# main.net
KiCad netlist of a schematic drawn in EAGLE
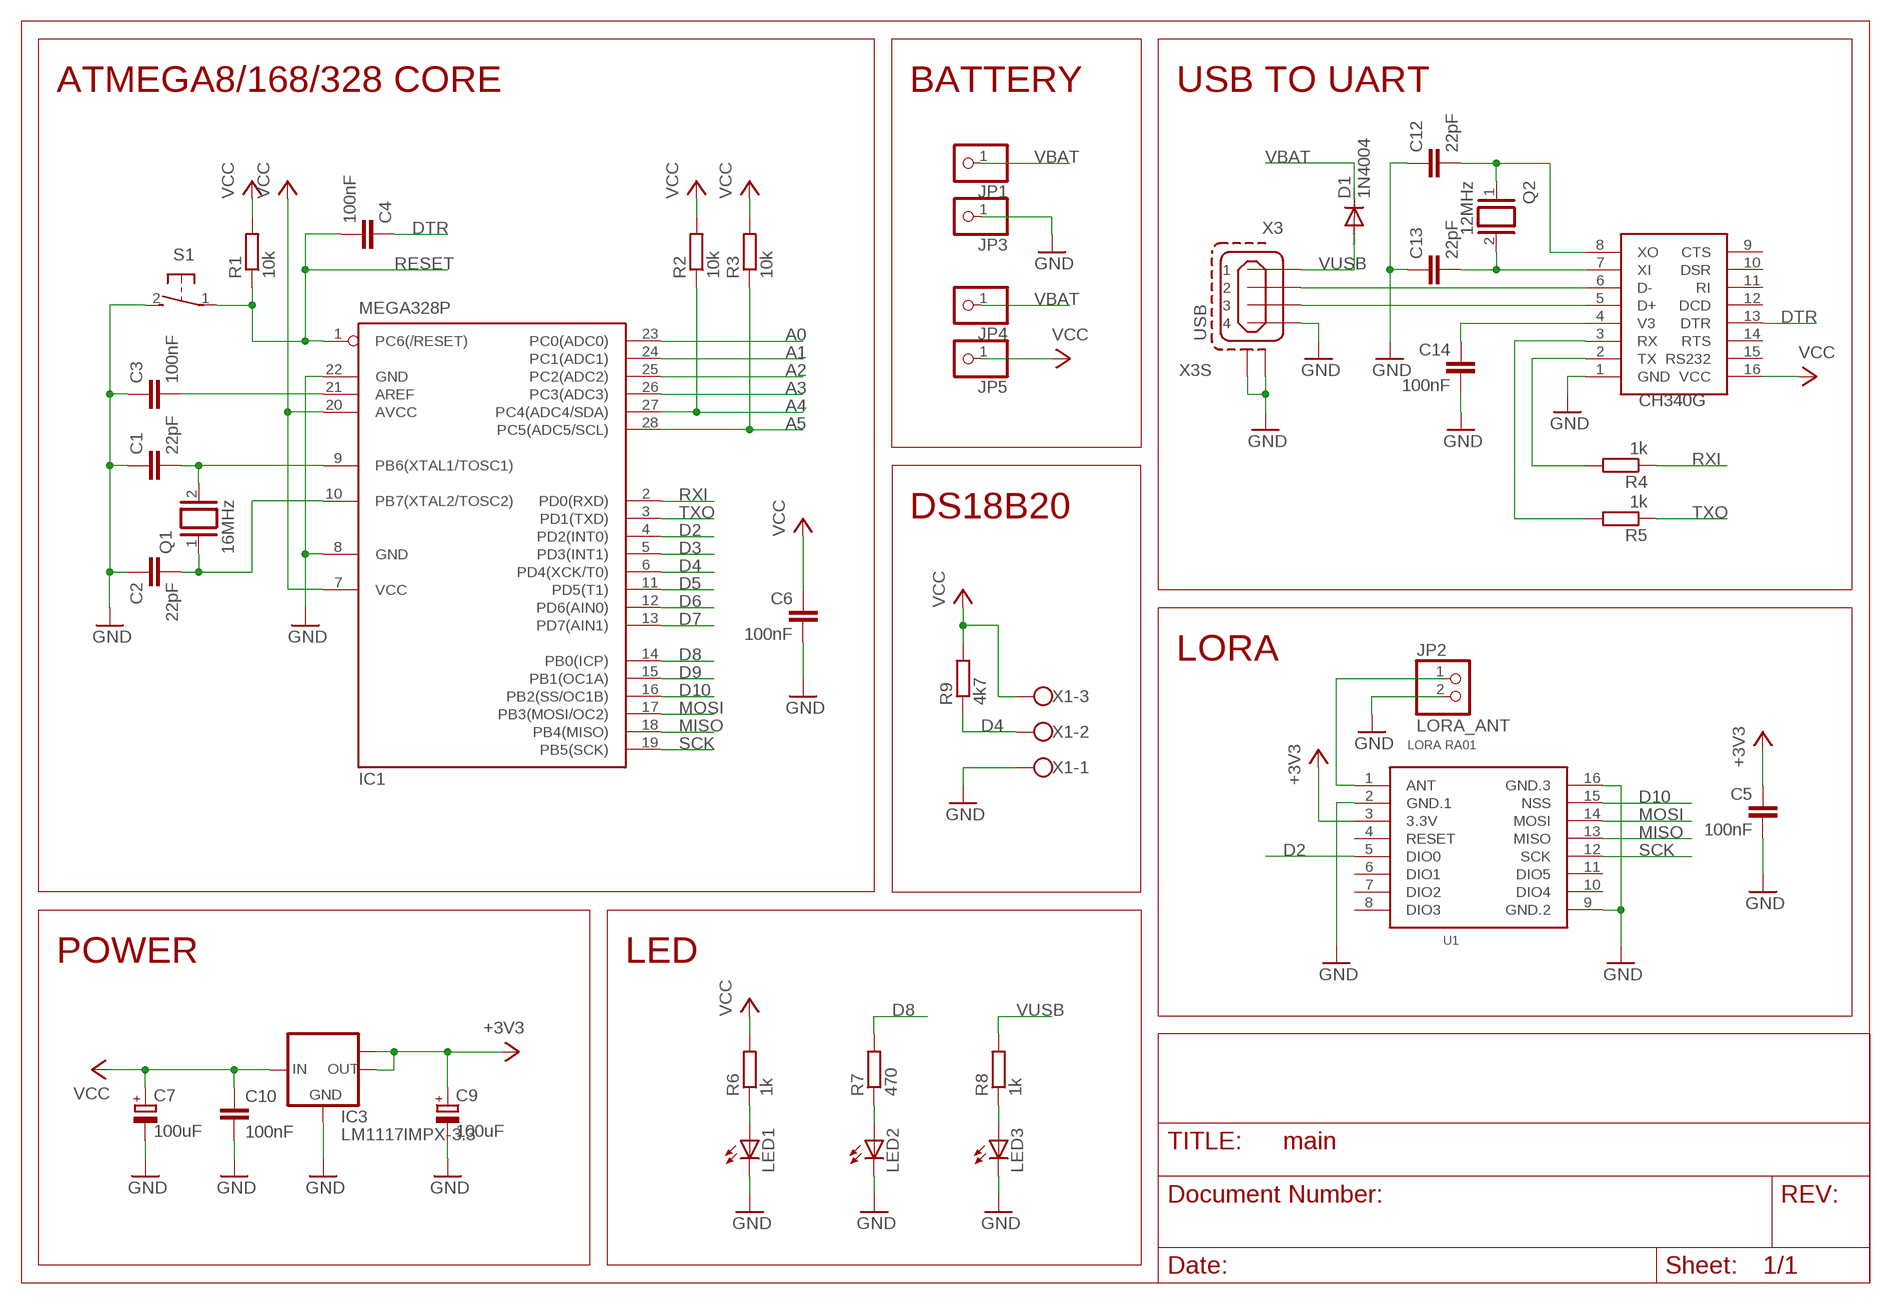
[diagram p0: schematic, sheet 1]

(export (version "E")
  (design (tool "Eeschema 10.0.6"))
  (components
    (comp (ref "C1")
      (value "22pF")
      (footprint "eagle-import:C050-024X044")
      (libsource (lib "eagle-import") (part "C-EU050-024X044"))
    )
    (comp (ref "C2")
      (value "22pF")
      (footprint "eagle-import:C050-024X044")
      (libsource (lib "eagle-import") (part "C-EU050-024X044"))
    )
    (comp (ref "C3")
      (value "100nF")
      (footprint "eagle-import:C050-024X044")
      (libsource (lib "eagle-import") (part "C-EU050-024X044"))
    )
    (comp (ref "C4")
      (value "100nF")
      (footprint "eagle-import:C050-024X044")
      (libsource (lib "eagle-import") (part "C-EU050-024X044"))
    )
    (comp (ref "C5")
      (value "100nF")
      (footprint "eagle-import:C050-024X044")
      (libsource (lib "eagle-import") (part "C-EU050-024X044"))
    )
    (comp (ref "C6")
      (value "100nF")
      (footprint "eagle-import:C050-024X044")
      (libsource (lib "eagle-import") (part "C-EU050-024X044"))
    )
    (comp (ref "C7")
      (value "100uF")
      (footprint "eagle-import:E3,5-10")
      (libsource (lib "eagle-import") (part "CPOL-EUE3.5-10"))
    )
    (comp (ref "C9")
      (value "100uF")
      (footprint "eagle-import:E3,5-8")
      (libsource (lib "eagle-import") (part "CPOL-EUE3.5-8"))
    )
    (comp (ref "C10")
      (value "100nF")
      (footprint "eagle-import:C050-024X044")
      (libsource (lib "eagle-import") (part "C-EU050-024X044"))
    )
    (comp (ref "C12")
      (value "22pF")
      (footprint "eagle-import:C050-024X044")
      (libsource (lib "eagle-import") (part "C-EU050-024X044"))
    )
    (comp (ref "C13")
      (value "22pF")
      (footprint "eagle-import:C050-024X044")
      (libsource (lib "eagle-import") (part "C-EU050-024X044"))
    )
    (comp (ref "C14")
      (value "100nF")
      (footprint "eagle-import:C050-024X044")
      (libsource (lib "eagle-import") (part "C-EU050-024X044"))
    )
    (comp (ref "D1")
      (value "1N4004")
      (footprint "eagle-import:DO41-10")
      (libsource (lib "eagle-import") (part "1N4004"))
    )
    (comp (ref "IC1")
      (value "MEGA328P")
      (footprint "eagle-import:DIL28-3")
      (libsource (lib "eagle-import") (part "MEGA8-P"))
    )
    (comp (ref "IC3")
      (value "LM1117IMPX-3.3")
      (footprint "eagle-import:SOT223")
      (libsource (lib "eagle-import") (part "LM1117IMPX-3.3"))
    )
    (comp (ref "JP1")
      (value "PINHD-1X1")
      (footprint "eagle-import:1X01")
      (libsource (lib "eagle-import") (part "PINHD-1X1"))
    )
    (comp (ref "JP2")
      (value "LORA_ANT")
      (footprint "eagle-import:1X02")
      (libsource (lib "eagle-import") (part "PINHD-1X2"))
    )
    (comp (ref "JP3")
      (value "PINHD-1X1")
      (footprint "eagle-import:1X01")
      (libsource (lib "eagle-import") (part "PINHD-1X1"))
    )
    (comp (ref "JP4")
      (value "PINHD-1X1")
      (footprint "eagle-import:1X01")
      (libsource (lib "eagle-import") (part "PINHD-1X1"))
    )
    (comp (ref "JP5")
      (value "PINHD-1X1")
      (footprint "eagle-import:1X01")
      (libsource (lib "eagle-import") (part "PINHD-1X1"))
    )
    (comp (ref "LED1")
      (value "LED3MM")
      (footprint "eagle-import:LED3MM")
      (libsource (lib "eagle-import") (part "LED3MM"))
    )
    (comp (ref "LED2")
      (value "LED3MM")
      (footprint "eagle-import:LED3MM")
      (libsource (lib "eagle-import") (part "LED3MM"))
    )
    (comp (ref "LED3")
      (value "LED3MM")
      (footprint "eagle-import:LED3MM")
      (libsource (lib "eagle-import") (part "LED3MM"))
    )
    (comp (ref "Q1")
      (value "16MHz")
      (footprint "eagle-import:QS")
      (libsource (lib "eagle-import") (part "XTAL/S"))
    )
    (comp (ref "Q2")
      (value "12MHz")
      (footprint "eagle-import:QS")
      (libsource (lib "eagle-import") (part "XTAL/S"))
    )
    (comp (ref "R1")
      (value "10k")
      (footprint "eagle-import:0207_10")
      (libsource (lib "eagle-import") (part "R-EU_0207/10"))
    )
    (comp (ref "R2")
      (value "10k")
      (footprint "eagle-import:0207_10")
      (libsource (lib "eagle-import") (part "R-EU_0207/10"))
    )
    (comp (ref "R3")
      (value "10k")
      (footprint "eagle-import:0207_10")
      (libsource (lib "eagle-import") (part "R-EU_0207/10"))
    )
    (comp (ref "R4")
      (value "1k")
      (footprint "eagle-import:0207_10")
      (libsource (lib "eagle-import") (part "R-EU_0207/10"))
    )
    (comp (ref "R5")
      (value "1k")
      (footprint "eagle-import:0207_10")
      (libsource (lib "eagle-import") (part "R-EU_0207/10"))
    )
    (comp (ref "R6")
      (value "1k")
      (footprint "eagle-import:0207_10")
      (libsource (lib "eagle-import") (part "R-EU_0207/10"))
    )
    (comp (ref "R7")
      (value "470")
      (footprint "eagle-import:0207_10")
      (libsource (lib "eagle-import") (part "R-EU_0207/10"))
    )
    (comp (ref "R8")
      (value "1k")
      (footprint "eagle-import:0207_10")
      (libsource (lib "eagle-import") (part "R-EU_0207/10"))
    )
    (comp (ref "R9")
      (value "4k7")
      (footprint "eagle-import:0207_10")
      (libsource (lib "eagle-import") (part "R-EU_0207/10"))
    )
    (comp (ref "S1")
      (value "31-XX")
      (footprint "eagle-import:B3F-31XX")
      (fields (field (name "MPN") "B3F-3100"))
      (libsource (lib "eagle-import") (part "31-XX"))
    )
    (comp (ref "U$1")
      (value "CH340G")
      (footprint "eagle-import:SOIC16")
      (libsource (lib "eagle-import") (part "CH340G"))
    )
    (comp (ref "U1")
      (value "LORA RA01")
      (footprint "eagle-import:LORA-RA1-SMD")
      (libsource (lib "eagle-import") (part "LORA-RA-01-433MHZ"))
    )
    (comp (ref "X1")
      (value "W237-103")
      (footprint "eagle-import:W237-103")
      (fields (field (name "MPN") "237-103"))
      (libsource (lib "eagle-import") (part "W237-103"))
    )
    (comp (ref "X3")
      (value "USB")
      (footprint "eagle-import:85-32004-00X")
      (libsource (lib "eagle-import") (part "MINI-USB_SHIELD4P-85-32004-00X"))
    )
  )
  (nets
    (net (code "1") (name "+3V3") (class "Default")
      (node (ref "C5") (pin "1") (pinfunction "1_1") (pintype "passive"))
      (node (ref "C9") (pin "+") (pinfunction "+_+") (pintype "passive"))
      (node (ref "IC3") (pin "2") (pinfunction "OUT_2") (pintype "passive"))
      (node (ref "IC3") (pin "TAB") (pinfunction "OUT1_TAB") (pintype "passive"))
      (node (ref "U1") (pin "3") (pinfunction "3.3V_3") (pintype "power_in"))
    )
    (net (code "2") (name "/A0") (class "Default")
      (node (ref "IC1") (pin "23") (pinfunction "PC0(ADC0)_23") (pintype "bidirectional"))
    )
    (net (code "3") (name "/A1") (class "Default")
      (node (ref "IC1") (pin "24") (pinfunction "PC1(ADC1)_24") (pintype "bidirectional"))
    )
    (net (code "4") (name "/A2") (class "Default")
      (node (ref "IC1") (pin "25") (pinfunction "PC2(ADC2)_25") (pintype "bidirectional"))
    )
    (net (code "5") (name "/A3") (class "Default")
      (node (ref "IC1") (pin "26") (pinfunction "PC3(ADC3)_26") (pintype "bidirectional"))
    )
    (net (code "6") (name "/A4") (class "Default")
      (node (ref "IC1") (pin "27") (pinfunction "PC4(ADC4/SDA)_27") (pintype "bidirectional"))
      (node (ref "R2") (pin "1") (pinfunction "1_1") (pintype "passive"))
    )
    (net (code "7") (name "/A5") (class "Default")
      (node (ref "IC1") (pin "28") (pinfunction "PC5(ADC5/SCL)_28") (pintype "bidirectional"))
      (node (ref "R3") (pin "1") (pinfunction "1_1") (pintype "passive"))
    )
    (net (code "8") (name "/D2") (class "Default")
      (node (ref "IC1") (pin "4") (pinfunction "PD2(INT0)_4") (pintype "bidirectional"))
      (node (ref "U1") (pin "5") (pinfunction "DIO0_5") (pintype "bidirectional"))
    )
    (net (code "9") (name "/D3") (class "Default")
      (node (ref "IC1") (pin "5") (pinfunction "PD3(INT1)_5") (pintype "bidirectional"))
    )
    (net (code "10") (name "/D4") (class "Default")
      (node (ref "IC1") (pin "6") (pinfunction "PD4(XCK/T0)_6") (pintype "bidirectional"))
      (node (ref "R9") (pin "1") (pinfunction "1_1") (pintype "passive"))
      (node (ref "X1") (pin "2") (pinfunction "KL_2") (pintype "passive"))
    )
    (net (code "11") (name "/D5") (class "Default")
      (node (ref "IC1") (pin "11") (pinfunction "PD5(T1)_11") (pintype "bidirectional"))
    )
    (net (code "12") (name "/D6") (class "Default")
      (node (ref "IC1") (pin "12") (pinfunction "PD6(AIN0)_12") (pintype "bidirectional"))
    )
    (net (code "13") (name "/D7") (class "Default")
      (node (ref "IC1") (pin "13") (pinfunction "PD7(AIN1)_13") (pintype "bidirectional"))
    )
    (net (code "14") (name "/D8") (class "Default")
      (node (ref "IC1") (pin "14") (pinfunction "PB0(ICP)_14") (pintype "bidirectional"))
      (node (ref "R7") (pin "2") (pinfunction "2_2") (pintype "passive"))
    )
    (net (code "15") (name "/D9") (class "Default")
      (node (ref "IC1") (pin "15") (pinfunction "PB1(OC1A)_15") (pintype "bidirectional"))
    )
    (net (code "16") (name "/D10") (class "Default")
      (node (ref "IC1") (pin "16") (pinfunction "PB2(SS/OC1B)_16") (pintype "bidirectional"))
      (node (ref "U1") (pin "15") (pinfunction "NSS_15") (pintype "bidirectional"))
    )
    (net (code "17") (name "/DTR") (class "Default")
      (node (ref "C4") (pin "1") (pinfunction "1_1") (pintype "passive"))
      (node (ref "U$1") (pin "13") (pinfunction "DTR_13") (pintype "bidirectional"))
    )
    (net (code "18") (name "/MISO") (class "Default")
      (node (ref "IC1") (pin "18") (pinfunction "PB4(MISO)_18") (pintype "bidirectional"))
      (node (ref "U1") (pin "13") (pinfunction "MISO_13") (pintype "bidirectional"))
    )
    (net (code "19") (name "/MOSI") (class "Default")
      (node (ref "IC1") (pin "17") (pinfunction "PB3(MOSI/OC2)_17") (pintype "bidirectional"))
      (node (ref "U1") (pin "14") (pinfunction "MOSI_14") (pintype "bidirectional"))
    )
    (net (code "20") (name "/RESET") (class "Default")
      (node (ref "C4") (pin "2") (pinfunction "2_2") (pintype "passive"))
      (node (ref "IC1") (pin "1") (pinfunction "PC6(/RESET)_1") (pintype "bidirectional"))
      (node (ref "R1") (pin "1") (pinfunction "1_1") (pintype "passive"))
      (node (ref "S1") (pin "1") (pinfunction "P_1") (pintype "passive"))
    )
    (net (code "21") (name "/RXI") (class "Default")
      (node (ref "IC1") (pin "2") (pinfunction "PD0(RXD)_2") (pintype "bidirectional"))
      (node (ref "R4") (pin "1") (pinfunction "1_1") (pintype "passive"))
    )
    (net (code "22") (name "/SCK") (class "Default")
      (node (ref "IC1") (pin "19") (pinfunction "PB5(SCK)_19") (pintype "bidirectional"))
      (node (ref "U1") (pin "12") (pinfunction "SCK_12") (pintype "bidirectional"))
    )
    (net (code "23") (name "/TXO") (class "Default")
      (node (ref "IC1") (pin "3") (pinfunction "PD1(TXD)_3") (pintype "bidirectional"))
      (node (ref "R5") (pin "1") (pinfunction "1_1") (pintype "passive"))
    )
    (net (code "24") (name "/VBAT") (class "Default")
      (node (ref "D1") (pin "C") (pinfunction "C_C") (pintype "passive"))
      (node (ref "JP1") (pin "1") (pinfunction "1_1") (pintype "passive"))
      (node (ref "JP4") (pin "1") (pinfunction "1_1") (pintype "passive"))
    )
    (net (code "25") (name "/VUSB") (class "Default")
      (node (ref "D1") (pin "A") (pinfunction "A_A") (pintype "passive"))
      (node (ref "R8") (pin "2") (pinfunction "2_2") (pintype "passive"))
      (node (ref "X3") (pin "1") (pinfunction "1_1") (pintype "passive"))
    )
    (net (code "26") (name "GND") (class "Default")
      (node (ref "C1") (pin "1") (pinfunction "1_1") (pintype "passive"))
      (node (ref "C10") (pin "2") (pinfunction "2_2") (pintype "passive"))
      (node (ref "C12") (pin "1") (pinfunction "1_1") (pintype "passive"))
      (node (ref "C13") (pin "1") (pinfunction "1_1") (pintype "passive"))
      (node (ref "C14") (pin "2") (pinfunction "2_2") (pintype "passive"))
      (node (ref "C2") (pin "1") (pinfunction "1_1") (pintype "passive"))
      (node (ref "C3") (pin "1") (pinfunction "1_1") (pintype "passive"))
      (node (ref "C5") (pin "2") (pinfunction "2_2") (pintype "passive"))
      (node (ref "C6") (pin "2") (pinfunction "2_2") (pintype "passive"))
      (node (ref "C7") (pin "-") (pinfunction "-_-") (pintype "passive"))
      (node (ref "C9") (pin "-") (pinfunction "-_-") (pintype "passive"))
      (node (ref "IC1") (pin "22") (pinfunction "GND_22") (pintype "power_in"))
      (node (ref "IC1") (pin "8") (pinfunction "GND_8") (pintype "power_in"))
      (node (ref "IC3") (pin "1") (pinfunction "GND_1") (pintype "input"))
      (node (ref "JP2") (pin "2") (pinfunction "2_2") (pintype "passive"))
      (node (ref "JP3") (pin "1") (pinfunction "1_1") (pintype "passive"))
      (node (ref "LED1") (pin "K") (pinfunction "C_K") (pintype "passive"))
      (node (ref "LED2") (pin "K") (pinfunction "C_K") (pintype "passive"))
      (node (ref "LED3") (pin "K") (pinfunction "C_K") (pintype "passive"))
      (node (ref "S1") (pin "2") (pinfunction "S_2") (pintype "passive"))
      (node (ref "U$1") (pin "1") (pinfunction "GND_1") (pintype "bidirectional"))
      (node (ref "U1") (pin "16") (pinfunction "GND.3_16") (pintype "power_in"))
      (node (ref "U1") (pin "2") (pinfunction "GND.1_2") (pintype "power_in"))
      (node (ref "U1") (pin "9") (pinfunction "GND.2_9") (pintype "power_in"))
      (node (ref "X1") (pin "1") (pinfunction "KL_1") (pintype "passive"))
      (node (ref "X3") (pin "4") (pinfunction "4_4") (pintype "passive"))
      (node (ref "X3") (pin "M1") (pinfunction "S1_M1") (pintype "passive"))
      (node (ref "X3") (pin "M2") (pinfunction "S2_M2") (pintype "passive"))
    )
    (net (code "27") (name "Net-(IC1-AREF)") (class "Default")
      (node (ref "C3") (pin "2") (pinfunction "2_2") (pintype "passive"))
      (node (ref "IC1") (pin "21") (pinfunction "AREF_21") (pintype "passive"))
    )
    (net (code "28") (name "Net-(IC1-PB6(XTAL1{slash}TOSC1))") (class "Default")
      (node (ref "C1") (pin "2") (pinfunction "2_2") (pintype "passive"))
      (node (ref "IC1") (pin "9") (pinfunction "PB6(XTAL1/TOSC1)_9") (pintype "bidirectional"))
      (node (ref "Q1") (pin "2") (pinfunction "2_2") (pintype "passive"))
    )
    (net (code "29") (name "Net-(IC1-PB7(XTAL2{slash}TOSC2))") (class "Default")
      (node (ref "C2") (pin "2") (pinfunction "2_2") (pintype "passive"))
      (node (ref "IC1") (pin "10") (pinfunction "PB7(XTAL2/TOSC2)_10") (pintype "bidirectional"))
      (node (ref "Q1") (pin "1") (pinfunction "1_1") (pintype "passive"))
    )
    (net (code "30") (name "Net-(LED1-PadA)") (class "Default")
      (node (ref "LED1") (pin "A") (pinfunction "A_A") (pintype "passive"))
      (node (ref "R6") (pin "1") (pinfunction "1_1") (pintype "passive"))
    )
    (net (code "31") (name "Net-(LED2-PadA)") (class "Default")
      (node (ref "LED2") (pin "A") (pinfunction "A_A") (pintype "passive"))
      (node (ref "R7") (pin "1") (pinfunction "1_1") (pintype "passive"))
    )
    (net (code "32") (name "Net-(LED3-PadA)") (class "Default")
      (node (ref "LED3") (pin "A") (pinfunction "A_A") (pintype "passive"))
      (node (ref "R8") (pin "1") (pinfunction "1_1") (pintype "passive"))
    )
    (net (code "33") (name "Net-(U$1-D+)") (class "Default")
      (node (ref "U$1") (pin "5") (pinfunction "D+_5") (pintype "bidirectional"))
      (node (ref "X3") (pin "3") (pinfunction "3_3") (pintype "passive"))
    )
    (net (code "34") (name "Net-(U$1-D-)") (class "Default")
      (node (ref "U$1") (pin "6") (pinfunction "D-_6") (pintype "bidirectional"))
      (node (ref "X3") (pin "2") (pinfunction "2_2") (pintype "passive"))
    )
    (net (code "35") (name "Net-(U$1-RX)") (class "Default")
      (node (ref "R5") (pin "2") (pinfunction "2_2") (pintype "passive"))
      (node (ref "U$1") (pin "3") (pinfunction "RX_3") (pintype "bidirectional"))
    )
    (net (code "36") (name "Net-(U$1-TX)") (class "Default")
      (node (ref "R4") (pin "2") (pinfunction "2_2") (pintype "passive"))
      (node (ref "U$1") (pin "2") (pinfunction "TX_2") (pintype "bidirectional"))
    )
    (net (code "37") (name "Net-(U$1-V3)") (class "Default")
      (node (ref "C14") (pin "1") (pinfunction "1_1") (pintype "passive"))
      (node (ref "U$1") (pin "4") (pinfunction "V3_4") (pintype "bidirectional"))
    )
    (net (code "38") (name "Net-(U$1-XI)") (class "Default")
      (node (ref "C13") (pin "2") (pinfunction "2_2") (pintype "passive"))
      (node (ref "Q2") (pin "2") (pinfunction "2_2") (pintype "passive"))
      (node (ref "U$1") (pin "7") (pinfunction "XI_7") (pintype "bidirectional"))
    )
    (net (code "39") (name "Net-(U$1-XO)") (class "Default")
      (node (ref "C12") (pin "2") (pinfunction "2_2") (pintype "passive"))
      (node (ref "Q2") (pin "1") (pinfunction "1_1") (pintype "passive"))
      (node (ref "U$1") (pin "8") (pinfunction "XO_8") (pintype "bidirectional"))
    )
    (net (code "40") (name "Net-(U1-ANT)") (class "Default")
      (node (ref "JP2") (pin "1") (pinfunction "1_1") (pintype "passive"))
      (node (ref "U1") (pin "1") (pinfunction "ANT_1") (pintype "bidirectional"))
    )
    (net (code "41") (name "VCC") (class "Default")
      (node (ref "C10") (pin "1") (pinfunction "1_1") (pintype "passive"))
      (node (ref "C6") (pin "1") (pinfunction "1_1") (pintype "passive"))
      (node (ref "C7") (pin "+") (pinfunction "+_+") (pintype "passive"))
      (node (ref "IC1") (pin "20") (pinfunction "AVCC_20") (pintype "power_in"))
      (node (ref "IC1") (pin "7") (pinfunction "VCC_7") (pintype "power_in"))
      (node (ref "IC3") (pin "3") (pinfunction "IN_3") (pintype "input"))
      (node (ref "JP5") (pin "1") (pinfunction "1_1") (pintype "passive"))
      (node (ref "R1") (pin "2") (pinfunction "2_2") (pintype "passive"))
      (node (ref "R2") (pin "2") (pinfunction "2_2") (pintype "passive"))
      (node (ref "R3") (pin "2") (pinfunction "2_2") (pintype "passive"))
      (node (ref "R6") (pin "2") (pinfunction "2_2") (pintype "passive"))
      (node (ref "R9") (pin "2") (pinfunction "2_2") (pintype "passive"))
      (node (ref "U$1") (pin "16") (pinfunction "VCC_16") (pintype "bidirectional"))
      (node (ref "X1") (pin "3") (pinfunction "KL_3") (pintype "passive"))
    )
    (net (code "42") (name "unconnected-(U$1-CTS-Pad9)") (class "Default")
      (node (ref "U$1") (pin "9") (pinfunction "CTS_9") (pintype "bidirectional"))
    )
    (net (code "43") (name "unconnected-(U$1-DCD-Pad12)") (class "Default")
      (node (ref "U$1") (pin "12") (pinfunction "DCD_12") (pintype "bidirectional"))
    )
    (net (code "44") (name "unconnected-(U$1-DSR-Pad10)") (class "Default")
      (node (ref "U$1") (pin "10") (pinfunction "DSR_10") (pintype "bidirectional"))
    )
    (net (code "45") (name "unconnected-(U$1-RI-Pad11)") (class "Default")
      (node (ref "U$1") (pin "11") (pinfunction "RI_11") (pintype "bidirectional"))
    )
    (net (code "46") (name "unconnected-(U$1-RS232-Pad15)") (class "Default")
      (node (ref "U$1") (pin "15") (pinfunction "RS232_15") (pintype "bidirectional"))
    )
    (net (code "47") (name "unconnected-(U$1-RTS-Pad14)") (class "Default")
      (node (ref "U$1") (pin "14") (pinfunction "RTS_14") (pintype "bidirectional"))
    )
    (net (code "48") (name "unconnected-(U1-DIO1-Pad6)") (class "Default")
      (node (ref "U1") (pin "6") (pinfunction "DIO1_6") (pintype "bidirectional"))
    )
    (net (code "49") (name "unconnected-(U1-DIO2-Pad7)") (class "Default")
      (node (ref "U1") (pin "7") (pinfunction "DIO2_7") (pintype "bidirectional"))
    )
    (net (code "50") (name "unconnected-(U1-DIO3-Pad8)") (class "Default")
      (node (ref "U1") (pin "8") (pinfunction "DIO3_8") (pintype "bidirectional"))
    )
    (net (code "51") (name "unconnected-(U1-DIO4-Pad10)") (class "Default")
      (node (ref "U1") (pin "10") (pinfunction "DIO4_10") (pintype "bidirectional"))
    )
    (net (code "52") (name "unconnected-(U1-DIO5-Pad11)") (class "Default")
      (node (ref "U1") (pin "11") (pinfunction "DIO5_11") (pintype "bidirectional"))
    )
    (net (code "53") (name "unconnected-(U1-RESET-Pad4)") (class "Default")
      (node (ref "U1") (pin "4") (pinfunction "RESET_4") (pintype "bidirectional"))
    )
  )
)
